# LTC3829_EVB.net
KiCad netlist of a schematic drawn in Altium Designer
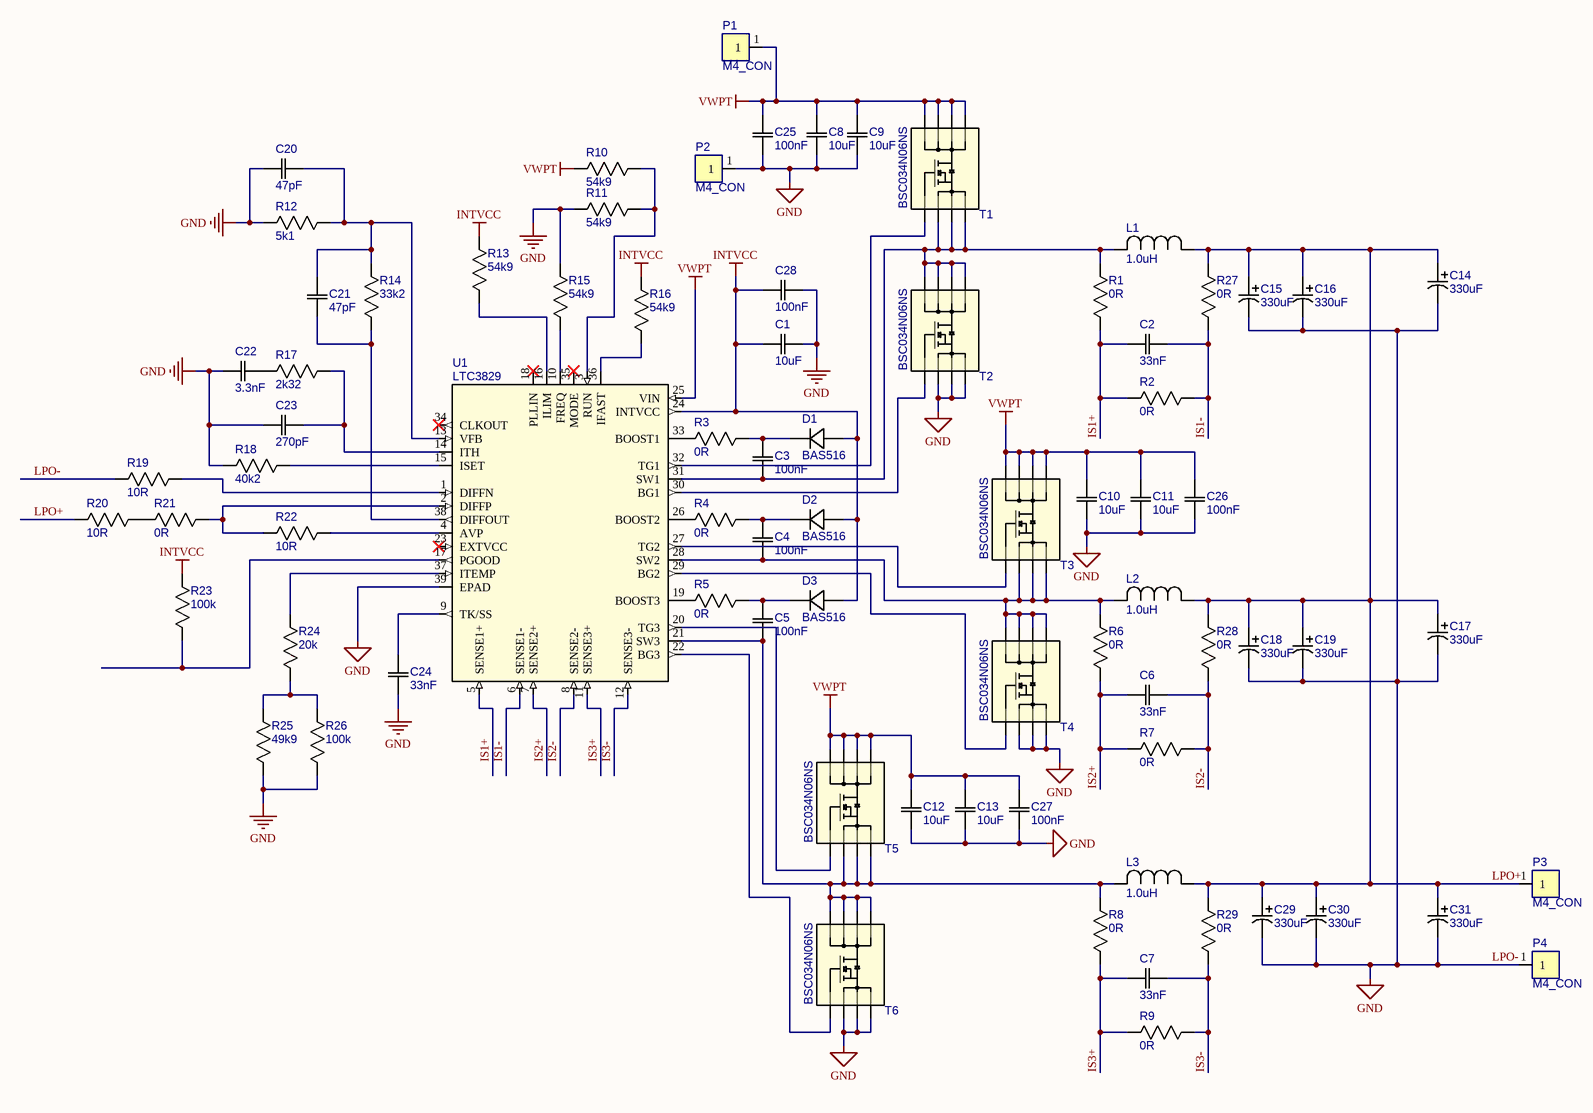
[diagram p0: LTC3829_EVB.SchDoc]

(export (version "E")
  (design (tool "Eeschema 10.0.6"))
  (components
    (comp (ref "C1")
      (value "10uF")
      (footprint "C0603")
      (description "OUDEIBUN\r\n25V 10% 106K X5R")
      (fields (field (name "MFR.") "OUDEIBUN"))
      (libsource (lib "C0603") (part "OUDEIBUN_10uF_25V"))
    )
    (comp (ref "C2")
      (value "33nF")
      (footprint "0402")
      (description "0402 33nF 333K 16V X7R")
      (fields (field (name "MFR.") "OBEIDUN"))
      (libsource (lib "C0402") (part "OBEIDUN_33nF"))
    )
    (comp (ref "C3")
      (value "100nF")
      (footprint "0402")
      (description "0402 100NF 104K  50V X7R")
      (fields (field (name "MFR.") "OBEIDUN"))
      (libsource (lib "C0402") (part "OBEIDUN_100nF"))
    )
    (comp (ref "C4")
      (value "100nF")
      (footprint "0402")
      (description "0402 100NF 104K  50V X7R")
      (fields (field (name "MFR.") "OBEIDUN"))
      (libsource (lib "C0402") (part "OBEIDUN_100nF"))
    )
    (comp (ref "C5")
      (value "100nF")
      (footprint "0402")
      (description "0402 100NF 104K  50V X7R")
      (fields (field (name "MFR.") "OBEIDUN"))
      (libsource (lib "C0402") (part "OBEIDUN_100nF"))
    )
    (comp (ref "C6")
      (value "33nF")
      (footprint "0402")
      (description "0402 33nF 333K 16V X7R")
      (fields (field (name "MFR.") "OBEIDUN"))
      (libsource (lib "C0402") (part "OBEIDUN_33nF"))
    )
    (comp (ref "C7")
      (value "33nF")
      (footprint "0402")
      (description "0402 33nF 333K 16V X7R")
      (fields (field (name "MFR.") "OBEIDUN"))
      (libsource (lib "C0402") (part "OBEIDUN_33nF"))
    )
    (comp (ref "C8")
      (value "10uF")
      (footprint "1210")
      (description "1210 10UF 106K 100V X7R")
      (fields (field (name "MFR.") "OUBEIDUN"))
      (libsource (lib "C1210") (part "OUBEIDUN_106_X7R"))
    )
    (comp (ref "C9")
      (value "10uF")
      (footprint "1210")
      (description "1210 10UF 106K 100V X7R")
      (fields (field (name "MFR.") "OUBEIDUN"))
      (libsource (lib "C1210") (part "OUBEIDUN_106_X7R"))
    )
    (comp (ref "C10")
      (value "10uF")
      (footprint "1210")
      (description "1210 10UF 106K 100V X7R")
      (fields (field (name "MFR.") "OUBEIDUN"))
      (libsource (lib "C1210") (part "OUBEIDUN_106_X7R"))
    )
    (comp (ref "C11")
      (value "10uF")
      (footprint "1210")
      (description "1210 10UF 106K 100V X7R")
      (fields (field (name "MFR.") "OUBEIDUN"))
      (libsource (lib "C1210") (part "OUBEIDUN_106_X7R"))
    )
    (comp (ref "C12")
      (value "10uF")
      (footprint "1210")
      (description "1210 10UF 106K 100V X7R")
      (fields (field (name "MFR.") "OUBEIDUN"))
      (libsource (lib "C1210") (part "OUBEIDUN_106_X7R"))
    )
    (comp (ref "C13")
      (value "10uF")
      (footprint "1210")
      (description "1210 10UF 106K 100V X7R")
      (fields (field (name "MFR.") "OUBEIDUN"))
      (libsource (lib "C1210") (part "OUBEIDUN_106_X7R"))
    )
    (comp (ref "C14")
      (value "330uF")
      (footprint "TAJD_AVX")
      (description "T520D337M006ATE010\r\n6.3V 330uF 2917 20% ESR=10mOhms")
      (fields (field (name "MFR.") "Auwah"))
      (libsource (lib "T520D337M006ATE010") (part "Auwah_330UF_7343"))
    )
    (comp (ref "C15")
      (value "330uF")
      (footprint "TAJD_AVX")
      (description "T520D337M006ATE010\r\n6.3V 330uF 2917 20% ESR=10mOhms")
      (fields (field (name "MFR.") "Auwah"))
      (libsource (lib "T520D337M006ATE010") (part "Auwah_330UF_7343"))
    )
    (comp (ref "C16")
      (value "330uF")
      (footprint "TAJD_AVX")
      (description "T520D337M006ATE010\r\n6.3V 330uF 2917 20% ESR=10mOhms")
      (fields (field (name "MFR.") "Auwah"))
      (libsource (lib "T520D337M006ATE010") (part "Auwah_330UF_7343"))
    )
    (comp (ref "C17")
      (value "330uF")
      (footprint "TAJD_AVX")
      (description "T520D337M006ATE010\r\n6.3V 330uF 2917 20% ESR=10mOhms")
      (fields (field (name "MFR.") "Auwah"))
      (libsource (lib "T520D337M006ATE010") (part "Auwah_330UF_7343"))
    )
    (comp (ref "C18")
      (value "330uF")
      (footprint "TAJD_AVX")
      (description "T520D337M006ATE010\r\n6.3V 330uF 2917 20% ESR=10mOhms")
      (fields (field (name "MFR.") "Auwah"))
      (libsource (lib "T520D337M006ATE010") (part "Auwah_330UF_7343"))
    )
    (comp (ref "C19")
      (value "330uF")
      (footprint "TAJD_AVX")
      (description "T520D337M006ATE010\r\n6.3V 330uF 2917 20% ESR=10mOhms")
      (fields (field (name "MFR.") "Auwah"))
      (libsource (lib "T520D337M006ATE010") (part "Auwah_330UF_7343"))
    )
    (comp (ref "C20")
      (value "47pF")
      (footprint "0402")
      (description "47pF 50V C0G CL05C470JB5NN4C")
      (fields (field (name "MFR.") "Samsung"))
      (libsource (lib "C0402") (part "taobao_47pF"))
    )
    (comp (ref "C21")
      (value "47pF")
      (footprint "0402")
      (description "47pF 50V C0G CL05C470JB5NN4C")
      (fields (field (name "MFR.") "Samsung"))
      (libsource (lib "C0402") (part "taobao_47pF"))
    )
    (comp (ref "C22")
      (value "3.3nF")
      (footprint "0402")
      (description "RAINPOLE 0402 3.3nF 5% 50V NPO")
      (fields (field (name "MFR.") "RAINPOLE"))
      (libsource (lib "C0402") (part "RAINPOLE_3n3F"))
    )
    (comp (ref "C23")
      (value "270pF")
      (footprint "0402")
      (description "0402 270PF 50V 271J COG NPO")
      (fields (field (name "MFR.") "OBEIDUN"))
      (libsource (lib "C0402") (part "OBEIDUN_270pF"))
    )
    (comp (ref "C24")
      (value "33nF")
      (footprint "0402")
      (description "0402 33nF 333K 16V X7R")
      (fields (field (name "MFR.") "OBEIDUN"))
      (libsource (lib "C0402") (part "OBEIDUN_33nF"))
    )
    (comp (ref "C25")
      (value "100nF")
      (footprint "C0603")
      (description "0603 100NF 50V 10% 104K X7R")
      (fields (field (name "MFR.") "OUDEIBUN"))
      (libsource (lib "C0603") (part "OUDEIBUN_100nF"))
    )
    (comp (ref "C26")
      (value "100nF")
      (footprint "C0603")
      (description "0603 100NF 50V 10% 104K X7R")
      (fields (field (name "MFR.") "OUDEIBUN"))
      (libsource (lib "C0603") (part "OUDEIBUN_100nF"))
    )
    (comp (ref "C27")
      (value "100nF")
      (footprint "C0603")
      (description "0603 100NF 50V 10% 104K X7R")
      (fields (field (name "MFR.") "OUDEIBUN"))
      (libsource (lib "C0603") (part "OUDEIBUN_100nF"))
    )
    (comp (ref "C28")
      (value "100nF")
      (footprint "0402")
      (description "0402 100NF 104K  50V X7R")
      (fields (field (name "MFR.") "OBEIDUN"))
      (libsource (lib "C0402") (part "OBEIDUN_100nF"))
    )
    (comp (ref "C29")
      (value "330uF")
      (footprint "TAJD_AVX")
      (description "T520D337M006ATE010\r\n6.3V 330uF 2917 20% ESR=10mOhms")
      (fields (field (name "MFR.") "Auwah"))
      (libsource (lib "T520D337M006ATE010") (part "Auwah_330UF_7343"))
    )
    (comp (ref "C30")
      (value "330uF")
      (footprint "TAJD_AVX")
      (description "T520D337M006ATE010\r\n6.3V 330uF 2917 20% ESR=10mOhms")
      (fields (field (name "MFR.") "Auwah"))
      (libsource (lib "T520D337M006ATE010") (part "Auwah_330UF_7343"))
    )
    (comp (ref "C31")
      (value "330uF")
      (footprint "TAJD_AVX")
      (description "T520D337M006ATE010\r\n6.3V 330uF 2917 20% ESR=10mOhms")
      (fields (field (name "MFR.") "Auwah"))
      (libsource (lib "T520D337M006ATE010") (part "Auwah_330UF_7343"))
    )
    (comp (ref "D1")
      (value "BAS516")
      (footprint "SOD-523")
      (description "SOD-523 100V/250mA")
      (fields (field (name "MFR.") "OBEIDUN"))
      (libsource (lib "BAS516") (part "OBEIDUN_BAS516"))
    )
    (comp (ref "D2")
      (value "BAS516")
      (footprint "SOD-523")
      (description "SOD-523 100V/250mA")
      (fields (field (name "MFR.") "OBEIDUN"))
      (libsource (lib "BAS516") (part "OBEIDUN_BAS516"))
    )
    (comp (ref "D3")
      (value "BAS516")
      (footprint "SOD-523")
      (description "SOD-523 100V/250mA")
      (fields (field (name "MFR.") "OBEIDUN"))
      (libsource (lib "BAS516") (part "OBEIDUN_BAS516"))
    )
    (comp (ref "L1")
      (value "1.0uH")
      (footprint "L126X")
      (description "HC1260 1R0M")
      (fields (field (name "MFR.") "HuiCi"))
      (libsource (lib "L12x0") (part "L1260_102"))
    )
    (comp (ref "L2")
      (value "1.0uH")
      (footprint "L126X")
      (description "HC1260 1R0M")
      (fields (field (name "MFR.") "HuiCi"))
      (libsource (lib "L12x0") (part "L1260_102"))
    )
    (comp (ref "L3")
      (value "1.0uH")
      (footprint "L126X")
      (description "HC1260 1R0M")
      (fields (field (name "MFR.") "HuiCi"))
      (libsource (lib "L12x0") (part "L1260_102"))
    )
    (comp (ref "P1")
      (value "M4_CON")
      (footprint "PCBComponent_1")
      (fields (field (name "MFR.") "LFX"))
      (libsource (lib "") (part "M4_CON_1"))
    )
    (comp (ref "P2")
      (value "M4_CON")
      (footprint "PCBComponent_1")
      (fields (field (name "MFR.") "LFX"))
      (libsource (lib "") (part "M4_CON_1"))
    )
    (comp (ref "P3")
      (value "M4_CON")
      (footprint "PCBComponent_1")
      (fields (field (name "MFR.") "LFX"))
      (libsource (lib "M4_CON") (part "M4_CON"))
    )
    (comp (ref "P4")
      (value "M4_CON")
      (footprint "PCBComponent_1")
      (fields (field (name "MFR.") "LFX"))
      (libsource (lib "M4_CON") (part "M4_CON"))
    )
    (comp (ref "R1")
      (value "0R")
      (footprint "0402")
      (description "OUDEIBUN\r\n0R 1% 1/16W")
      (fields (field (name "MFR.") "OUDEIBUN"))
      (libsource (lib "R0402") (part "OUDEIBUN_0R"))
    )
    (comp (ref "R2")
      (value "0R")
      (footprint "0402")
      (description "OUDEIBUN\r\n0R 1% 1/16W")
      (fields (field (name "MFR.") "OUDEIBUN"))
      (libsource (lib "R0402") (part "OUDEIBUN_0R"))
    )
    (comp (ref "R3")
      (value "0R")
      (footprint "0603")
      (description "0R 1/10W +/-1%")
      (fields (field (name "MFR.") "UNIOHM"))
      (libsource (lib "R0603") (part "0R"))
    )
    (comp (ref "R4")
      (value "0R")
      (footprint "0603")
      (description "0R 1/10W +/-1%")
      (fields (field (name "MFR.") "UNIOHM"))
      (libsource (lib "R0603") (part "0R"))
    )
    (comp (ref "R5")
      (value "0R")
      (footprint "0603")
      (description "0R 1/10W +/-1%")
      (fields (field (name "MFR.") "UNIOHM"))
      (libsource (lib "R0603") (part "0R"))
    )
    (comp (ref "R6")
      (value "0R")
      (footprint "0402")
      (description "OUDEIBUN\r\n0R 1% 1/16W")
      (fields (field (name "MFR.") "OUDEIBUN"))
      (libsource (lib "R0402") (part "OUDEIBUN_0R"))
    )
    (comp (ref "R7")
      (value "0R")
      (footprint "0402")
      (description "OUDEIBUN\r\n0R 1% 1/16W")
      (fields (field (name "MFR.") "OUDEIBUN"))
      (libsource (lib "R0402") (part "OUDEIBUN_0R"))
    )
    (comp (ref "R8")
      (value "0R")
      (footprint "0402")
      (description "OUDEIBUN\r\n0R 1% 1/16W")
      (fields (field (name "MFR.") "OUDEIBUN"))
      (libsource (lib "R0402") (part "OUDEIBUN_0R"))
    )
    (comp (ref "R9")
      (value "0R")
      (footprint "0402")
      (description "OUDEIBUN\r\n0R 1% 1/16W")
      (fields (field (name "MFR.") "OUDEIBUN"))
      (libsource (lib "R0402") (part "OUDEIBUN_0R"))
    )
    (comp (ref "R10")
      (value "54k9")
      (footprint "0402")
      (description "OUDEIBUN\r\n54k9 1% 1/16W")
      (fields (field (name "MFR.") "OUDEIBUN"))
      (libsource (lib "R0402") (part "OUDEIBUN_54k9"))
    )
    (comp (ref "R11")
      (value "54k9")
      (footprint "0402")
      (description "OUDEIBUN\r\n54k9 1% 1/16W")
      (fields (field (name "MFR.") "OUDEIBUN"))
      (libsource (lib "R0402") (part "OUDEIBUN_54k9"))
    )
    (comp (ref "R12")
      (value "5k1")
      (footprint "0402")
      (description "UNIOHM\r\n5k1 1% 1/16W")
      (fields (field (name "MFR.") "UNIOHM"))
      (libsource (lib "R0402") (part "UNIOHM_5k1"))
    )
    (comp (ref "R13")
      (value "54k9")
      (footprint "0402")
      (description "OUDEIBUN\r\n54k9 1% 1/16W")
      (fields (field (name "MFR.") "OUDEIBUN"))
      (libsource (lib "R0402") (part "OUDEIBUN_54k9"))
    )
    (comp (ref "R14")
      (value "33k2")
      (footprint "0402")
      (description "OUDEIBUN\r\n33k2 1% 1/16W")
      (fields (field (name "MFR.") "OUDEIBUN"))
      (libsource (lib "R0402") (part "OUDEIBUN_33k2"))
    )
    (comp (ref "R15")
      (value "54k9")
      (footprint "0402")
      (description "OUDEIBUN\r\n54k9 1% 1/16W")
      (fields (field (name "MFR.") "OUDEIBUN"))
      (libsource (lib "R0402") (part "OUDEIBUN_54k9"))
    )
    (comp (ref "R16")
      (value "54k9")
      (footprint "0402")
      (description "OUDEIBUN\r\n54k9 1% 1/16W")
      (fields (field (name "MFR.") "OUDEIBUN"))
      (libsource (lib "R0402") (part "OUDEIBUN_54k9"))
    )
    (comp (ref "R17")
      (value "2k32")
      (footprint "0402")
      (description "OUDEIBUN\r\n1% 2k32")
      (fields (field (name "MFR.") "OUDEIBUN"))
      (libsource (lib "R0402") (part "OUDEIBUN_2k32"))
    )
    (comp (ref "R18")
      (value "40k2")
      (footprint "0402")
      (description "UNIOHM\r\n40k2 1% 1/16W")
      (fields (field (name "MFR.") "UNIOHM"))
      (libsource (lib "R0402") (part "UNIOHM_40k2"))
    )
    (comp (ref "R19")
      (value "10R")
      (footprint "0402")
      (description "OUDEIBUN\r\n10R 1% 1/16W")
      (fields (field (name "MFR.") "OUDEIBUN"))
      (libsource (lib "R0402") (part "OUDEIBUN_10R"))
    )
    (comp (ref "R20")
      (value "10R")
      (footprint "0402")
      (description "OUDEIBUN\r\n10R 1% 1/16W")
      (fields (field (name "MFR.") "OUDEIBUN"))
      (libsource (lib "R0402") (part "OUDEIBUN_10R"))
    )
    (comp (ref "R21")
      (value "0R")
      (footprint "0402")
      (description "OUDEIBUN\r\n0R 1% 1/16W")
      (fields (field (name "MFR.") "OUDEIBUN"))
      (libsource (lib "R0402") (part "OUDEIBUN_0R"))
    )
    (comp (ref "R22")
      (value "10R")
      (footprint "0603")
      (description "10R 1/10W +/-0.5%")
      (fields (field (name "MFR.") "Viking"))
      (libsource (lib "R0603") (part "ARG03DTC0100"))
    )
    (comp (ref "R23")
      (value "100k")
      (footprint "0402")
      (description "OUDEIBUN\r\n1% 100k")
      (fields (field (name "MFR.") "UNIOHM"))
      (libsource (lib "R0402") (part "OUDEIBUN_100k"))
    )
    (comp (ref "R24")
      (value "20k")
      (footprint "0402")
      (description "OUDEIBUN\r\n20k 1% 1/16W")
      (fields (field (name "MFR.") "OUDEIBUN"))
      (libsource (lib "R0402") (part "OUDEIBUN_20k"))
    )
    (comp (ref "R25")
      (value "49k9")
      (footprint "0402")
      (description "OUDEIBUN\r\n1% 49k9")
      (fields (field (name "MFR.") "OUDEIBUN"))
      (libsource (lib "R0402") (part "OUDEIBUN_49k9"))
    )
    (comp (ref "R26")
      (value "100k")
      (footprint "0402")
      (description "OUDEIBUN\r\n1% 100k")
      (fields (field (name "MFR.") "UNIOHM"))
      (libsource (lib "R0402") (part "OUDEIBUN_100k"))
    )
    (comp (ref "R27")
      (value "0R")
      (footprint "0402")
      (description "OUDEIBUN\r\n0R 1% 1/16W")
      (fields (field (name "MFR.") "OUDEIBUN"))
      (libsource (lib "R0402") (part "OUDEIBUN_0R"))
    )
    (comp (ref "R28")
      (value "0R")
      (footprint "0402")
      (description "OUDEIBUN\r\n0R 1% 1/16W")
      (fields (field (name "MFR.") "OUDEIBUN"))
      (libsource (lib "R0402") (part "OUDEIBUN_0R"))
    )
    (comp (ref "R29")
      (value "0R")
      (footprint "0402")
      (description "OUDEIBUN\r\n0R 1% 1/16W")
      (fields (field (name "MFR.") "OUDEIBUN"))
      (libsource (lib "R0402") (part "OUDEIBUN_0R"))
    )
    (comp (ref "T1")
      (value "BSC034N06NS")
      (footprint "PQFNWB5x6")
      (description "MPower Transistor, 60V")
      (fields (field (name "MFR.") "Infineon Technologies"))
      (libsource (lib "MOS_PQFNWB5x6") (part "BSC034N06NS"))
    )
    (comp (ref "T2")
      (value "BSC034N06NS")
      (footprint "PQFNWB5x6")
      (description "MPower Transistor, 60V")
      (fields (field (name "MFR.") "Infineon Technologies"))
      (libsource (lib "MOS_PQFNWB5x6") (part "BSC034N06NS"))
    )
    (comp (ref "T3")
      (value "BSC034N06NS")
      (footprint "PQFNWB5x6")
      (description "MPower Transistor, 60V")
      (fields (field (name "MFR.") "Infineon Technologies"))
      (libsource (lib "MOS_PQFNWB5x6") (part "BSC034N06NS"))
    )
    (comp (ref "T4")
      (value "BSC034N06NS")
      (footprint "PQFNWB5x6")
      (description "MPower Transistor, 60V")
      (fields (field (name "MFR.") "Infineon Technologies"))
      (libsource (lib "MOS_PQFNWB5x6") (part "BSC034N06NS"))
    )
    (comp (ref "T5")
      (value "BSC034N06NS")
      (footprint "PQFNWB5x6")
      (description "MPower Transistor, 60V")
      (fields (field (name "MFR.") "Infineon Technologies"))
      (libsource (lib "MOS_PQFNWB5x6") (part "BSC034N06NS"))
    )
    (comp (ref "T6")
      (value "BSC034N06NS")
      (footprint "PQFNWB5x6")
      (description "MPower Transistor, 60V")
      (fields (field (name "MFR.") "Infineon Technologies"))
      (libsource (lib "MOS_PQFNWB5x6") (part "BSC034N06NS"))
    )
    (comp (ref "U1")
      (value "LTC3829")
      (footprint "QFN-38")
      (description "3-Phase, Single Output Synchronous\r\nStep-Down DC/DC Controller with Diffamp")
      (fields (field (name "MFR.") "Analog Devices Inc"))
      (libsource (lib "LTC3829") (part "LTC3829EUHFPBF"))
    )
  )
  (nets
    (net (code "1") (name "/IS1+") (class "Default")
      (node (ref "C2") (pin "1") (pinfunction "1_1") (pintype "passive"))
      (node (ref "R1") (pin "1") (pinfunction "1_1") (pintype "passive"))
      (node (ref "R2") (pin "2") (pinfunction "2_2") (pintype "passive"))
      (node (ref "U1") (pin "5") (pinfunction "SENSE1+_5") (pintype "input"))
    )
    (net (code "2") (name "/IS1-") (class "Default")
      (node (ref "C2") (pin "2") (pinfunction "2_2") (pintype "passive"))
      (node (ref "R2") (pin "1") (pinfunction "1_1") (pintype "passive"))
      (node (ref "R27") (pin "1") (pinfunction "1_1") (pintype "passive"))
      (node (ref "U1") (pin "6") (pinfunction "SENSE1-_6") (pintype "input"))
    )
    (net (code "3") (name "/IS2+") (class "Default")
      (node (ref "C6") (pin "1") (pinfunction "1_1") (pintype "passive"))
      (node (ref "R6") (pin "1") (pinfunction "1_1") (pintype "passive"))
      (node (ref "R7") (pin "2") (pinfunction "2_2") (pintype "passive"))
      (node (ref "U1") (pin "7") (pinfunction "SENSE2+_7") (pintype "input"))
    )
    (net (code "4") (name "/IS2-") (class "Default")
      (node (ref "C6") (pin "2") (pinfunction "2_2") (pintype "passive"))
      (node (ref "R28") (pin "1") (pinfunction "1_1") (pintype "passive"))
      (node (ref "R7") (pin "1") (pinfunction "1_1") (pintype "passive"))
      (node (ref "U1") (pin "8") (pinfunction "SENSE2-_8") (pintype "input"))
    )
    (net (code "5") (name "/IS3+") (class "Default")
      (node (ref "C7") (pin "1") (pinfunction "1_1") (pintype "passive"))
      (node (ref "R8") (pin "1") (pinfunction "1_1") (pintype "passive"))
      (node (ref "R9") (pin "2") (pinfunction "2_2") (pintype "passive"))
      (node (ref "U1") (pin "11") (pinfunction "SENSE3+_11") (pintype "input"))
    )
    (net (code "6") (name "/IS3-") (class "Default")
      (node (ref "C7") (pin "2") (pinfunction "2_2") (pintype "passive"))
      (node (ref "R29") (pin "1") (pinfunction "1_1") (pintype "passive"))
      (node (ref "R9") (pin "1") (pinfunction "1_1") (pintype "passive"))
      (node (ref "U1") (pin "12") (pinfunction "SENSE3-_12") (pintype "input"))
    )
    (net (code "7") (name "/LPO+") (class "Default")
      (node (ref "C14") (pin "1") (pinfunction "11_1") (pintype "passive"))
      (node (ref "C15") (pin "1") (pinfunction "11_1") (pintype "passive"))
      (node (ref "C16") (pin "1") (pinfunction "11_1") (pintype "passive"))
      (node (ref "C17") (pin "1") (pinfunction "11_1") (pintype "passive"))
      (node (ref "C18") (pin "1") (pinfunction "11_1") (pintype "passive"))
      (node (ref "C19") (pin "1") (pinfunction "11_1") (pintype "passive"))
      (node (ref "C29") (pin "1") (pinfunction "11_1") (pintype "passive"))
      (node (ref "C30") (pin "1") (pinfunction "11_1") (pintype "passive"))
      (node (ref "C31") (pin "1") (pinfunction "11_1") (pintype "passive"))
      (node (ref "L1") (pin "1") (pinfunction "1_1") (pintype "passive"))
      (node (ref "L2") (pin "1") (pinfunction "1_1") (pintype "passive"))
      (node (ref "L3") (pin "1") (pinfunction "1_1") (pintype "passive"))
      (node (ref "P3") (pin "1") (pinfunction "1_1") (pintype "passive"))
      (node (ref "R20") (pin "1") (pinfunction "1_1") (pintype "passive"))
      (node (ref "R27") (pin "2") (pinfunction "2_2") (pintype "passive"))
      (node (ref "R28") (pin "2") (pinfunction "2_2") (pintype "passive"))
      (node (ref "R29") (pin "2") (pinfunction "2_2") (pintype "passive"))
    )
    (net (code "8") (name "GND") (class "Default")
      (node (ref "C1") (pin "2") (pinfunction "2_2") (pintype "passive"))
      (node (ref "C10") (pin "1") (pinfunction "11_1") (pintype "passive"))
      (node (ref "C11") (pin "1") (pinfunction "11_1") (pintype "passive"))
      (node (ref "C12") (pin "1") (pinfunction "11_1") (pintype "passive"))
      (node (ref "C13") (pin "1") (pinfunction "11_1") (pintype "passive"))
      (node (ref "C14") (pin "2") (pinfunction "12_2") (pintype "passive"))
      (node (ref "C15") (pin "2") (pinfunction "12_2") (pintype "passive"))
      (node (ref "C16") (pin "2") (pinfunction "12_2") (pintype "passive"))
      (node (ref "C17") (pin "2") (pinfunction "12_2") (pintype "passive"))
      (node (ref "C18") (pin "2") (pinfunction "12_2") (pintype "passive"))
      (node (ref "C19") (pin "2") (pinfunction "12_2") (pintype "passive"))
      (node (ref "C20") (pin "1") (pinfunction "1_1") (pintype "passive"))
      (node (ref "C22") (pin "1") (pinfunction "1_1") (pintype "passive"))
      (node (ref "C23") (pin "1") (pinfunction "1_1") (pintype "passive"))
      (node (ref "C24") (pin "1") (pinfunction "1_1") (pintype "passive"))
      (node (ref "C25") (pin "1") (pinfunction "1_1") (pintype "passive"))
      (node (ref "C26") (pin "1") (pinfunction "1_1") (pintype "passive"))
      (node (ref "C27") (pin "1") (pinfunction "1_1") (pintype "passive"))
      (node (ref "C28") (pin "1") (pinfunction "1_1") (pintype "passive"))
      (node (ref "C29") (pin "2") (pinfunction "12_2") (pintype "passive"))
      (node (ref "C30") (pin "2") (pinfunction "12_2") (pintype "passive"))
      (node (ref "C31") (pin "2") (pinfunction "12_2") (pintype "passive"))
      (node (ref "C8") (pin "1") (pinfunction "11_1") (pintype "passive"))
      (node (ref "C9") (pin "1") (pinfunction "11_1") (pintype "passive"))
      (node (ref "P2") (pin "1") (pinfunction "1_1") (pintype "passive"))
      (node (ref "P4") (pin "1") (pinfunction "1_1") (pintype "passive"))
      (node (ref "R11") (pin "2") (pinfunction "2_2") (pintype "passive"))
      (node (ref "R12") (pin "1") (pinfunction "1_1") (pintype "passive"))
      (node (ref "R15") (pin "2") (pinfunction "2_2") (pintype "passive"))
      (node (ref "R18") (pin "1") (pinfunction "1_1") (pintype "passive"))
      (node (ref "R19") (pin "1") (pinfunction "1_1") (pintype "passive"))
      (node (ref "R25") (pin "1") (pinfunction "1_1") (pintype "passive"))
      (node (ref "R26") (pin "1") (pinfunction "1_1") (pintype "passive"))
      (node (ref "T2") (pin "1") (pinfunction "1_1") (pintype "passive"))
      (node (ref "T2") (pin "2") (pinfunction "2_2") (pintype "passive"))
      (node (ref "T2") (pin "3") (pinfunction "3_3") (pintype "passive"))
      (node (ref "T4") (pin "1") (pinfunction "1_1") (pintype "passive"))
      (node (ref "T4") (pin "2") (pinfunction "2_2") (pintype "passive"))
      (node (ref "T4") (pin "3") (pinfunction "3_3") (pintype "passive"))
      (node (ref "T6") (pin "1") (pinfunction "1_1") (pintype "passive"))
      (node (ref "T6") (pin "2") (pinfunction "2_2") (pintype "passive"))
      (node (ref "T6") (pin "3") (pinfunction "3_3") (pintype "passive"))
      (node (ref "U1") (pin "39") (pinfunction "EPAD_39") (pintype "passive"))
    )
    (net (code "9") (name "INTVCC") (class "Default")
      (node (ref "C1") (pin "1") (pinfunction "1_1") (pintype "passive"))
      (node (ref "C28") (pin "2") (pinfunction "2_2") (pintype "passive"))
      (node (ref "D1") (pin "2") (pinfunction "2_2") (pintype "passive"))
      (node (ref "D2") (pin "2") (pinfunction "2_2") (pintype "passive"))
      (node (ref "D3") (pin "2") (pinfunction "2_2") (pintype "passive"))
      (node (ref "R13") (pin "2") (pinfunction "2_2") (pintype "passive"))
      (node (ref "R16") (pin "2") (pinfunction "2_2") (pintype "passive"))
      (node (ref "R23") (pin "2") (pinfunction "2_2") (pintype "passive"))
      (node (ref "U1") (pin "24") (pinfunction "INTVCC_24") (pintype "output"))
    )
    (net (code "10") (name "Net-(C3-Pad2)") (class "Default")
      (node (ref "C3") (pin "2") (pinfunction "2_2") (pintype "passive"))
      (node (ref "D1") (pin "1") (pinfunction "1_1") (pintype "passive"))
      (node (ref "R3") (pin "2") (pinfunction "2_2") (pintype "passive"))
    )
    (net (code "11") (name "Net-(C4-Pad2)") (class "Default")
      (node (ref "C4") (pin "2") (pinfunction "2_2") (pintype "passive"))
      (node (ref "D2") (pin "1") (pinfunction "1_1") (pintype "passive"))
      (node (ref "R4") (pin "2") (pinfunction "2_2") (pintype "passive"))
    )
    (net (code "12") (name "Net-(C5-Pad2)") (class "Default")
      (node (ref "C5") (pin "2") (pinfunction "2_2") (pintype "passive"))
      (node (ref "D3") (pin "1") (pinfunction "1_1") (pintype "passive"))
      (node (ref "R5") (pin "2") (pinfunction "2_2") (pintype "passive"))
    )
    (net (code "13") (name "Net-(C22-Pad2)") (class "Default")
      (node (ref "C22") (pin "2") (pinfunction "2_2") (pintype "passive"))
      (node (ref "R17") (pin "1") (pinfunction "1_1") (pintype "passive"))
    )
    (net (code "14") (name "Net-(R20-Pad2)") (class "Default")
      (node (ref "R20") (pin "2") (pinfunction "2_2") (pintype "passive"))
      (node (ref "R21") (pin "1") (pinfunction "1_1") (pintype "passive"))
    )
    (net (code "15") (name "Net-(R24-Pad1)") (class "Default")
      (node (ref "R24") (pin "1") (pinfunction "1_1") (pintype "passive"))
      (node (ref "R25") (pin "2") (pinfunction "2_2") (pintype "passive"))
      (node (ref "R26") (pin "2") (pinfunction "2_2") (pintype "passive"))
    )
    (net (code "16") (name "Net-(U1-AVP)") (class "Default")
      (node (ref "R22") (pin "2") (pinfunction "2_2") (pintype "passive"))
      (node (ref "U1") (pin "4") (pinfunction "AVP_4") (pintype "passive"))
    )
    (net (code "17") (name "Net-(U1-BG1)") (class "Default")
      (node (ref "T2") (pin "4") (pinfunction "4_4") (pintype "passive"))
      (node (ref "U1") (pin "30") (pinfunction "BG1_30") (pintype "output"))
    )
    (net (code "18") (name "Net-(U1-BG2)") (class "Default")
      (node (ref "T4") (pin "4") (pinfunction "4_4") (pintype "passive"))
      (node (ref "U1") (pin "29") (pinfunction "BG2_29") (pintype "output"))
    )
    (net (code "19") (name "Net-(U1-BG3)") (class "Default")
      (node (ref "T6") (pin "4") (pinfunction "4_4") (pintype "passive"))
      (node (ref "U1") (pin "22") (pinfunction "BG3_22") (pintype "output"))
    )
    (net (code "20") (name "Net-(U1-BOOST1)") (class "Default")
      (node (ref "R3") (pin "1") (pinfunction "1_1") (pintype "passive"))
      (node (ref "U1") (pin "33") (pinfunction "BOOST1_33") (pintype "passive"))
    )
    (net (code "21") (name "Net-(U1-BOOST2)") (class "Default")
      (node (ref "R4") (pin "1") (pinfunction "1_1") (pintype "passive"))
      (node (ref "U1") (pin "26") (pinfunction "BOOST2_26") (pintype "passive"))
    )
    (net (code "22") (name "Net-(U1-BOOST3)") (class "Default")
      (node (ref "R5") (pin "1") (pinfunction "1_1") (pintype "passive"))
      (node (ref "U1") (pin "19") (pinfunction "BOOST3_19") (pintype "passive"))
    )
    (net (code "23") (name "Net-(U1-DIFFN)") (class "Default")
      (node (ref "R19") (pin "2") (pinfunction "2_2") (pintype "passive"))
      (node (ref "U1") (pin "1") (pinfunction "DIFFN_1") (pintype "input"))
    )
    (net (code "24") (name "Net-(U1-DIFFOUT)") (class "Default")
      (node (ref "C21") (pin "1") (pinfunction "1_1") (pintype "passive"))
      (node (ref "R14") (pin "1") (pinfunction "1_1") (pintype "passive"))
      (node (ref "U1") (pin "38") (pinfunction "DIFFOUT_38") (pintype "output"))
    )
    (net (code "25") (name "Net-(U1-DIFFP)") (class "Default")
      (node (ref "R21") (pin "2") (pinfunction "2_2") (pintype "passive"))
      (node (ref "R22") (pin "1") (pinfunction "1_1") (pintype "passive"))
      (node (ref "U1") (pin "2") (pinfunction "DIFFP_2") (pintype "input"))
    )
    (net (code "26") (name "Net-(U1-FREQ)") (class "Default")
      (node (ref "R15") (pin "1") (pinfunction "1_1") (pintype "passive"))
      (node (ref "U1") (pin "10") (pinfunction "FREQ_10") (pintype "passive"))
    )
    (net (code "27") (name "Net-(U1-IFAST)") (class "Default")
      (node (ref "R16") (pin "1") (pinfunction "1_1") (pintype "passive"))
      (node (ref "U1") (pin "36") (pinfunction "IFAST_36") (pintype "passive"))
    )
    (net (code "28") (name "Net-(U1-ILIM)") (class "Default")
      (node (ref "R13") (pin "1") (pinfunction "1_1") (pintype "passive"))
      (node (ref "U1") (pin "16") (pinfunction "ILIM_16") (pintype "passive"))
    )
    (net (code "29") (name "Net-(U1-ISET)") (class "Default")
      (node (ref "R18") (pin "2") (pinfunction "2_2") (pintype "passive"))
      (node (ref "U1") (pin "15") (pinfunction "ISET_15") (pintype "passive"))
    )
    (net (code "30") (name "Net-(U1-ITEMP)") (class "Default")
      (node (ref "R24") (pin "2") (pinfunction "2_2") (pintype "passive"))
      (node (ref "U1") (pin "37") (pinfunction "ITEMP_37") (pintype "input"))
    )
    (net (code "31") (name "Net-(U1-ITH)") (class "Default")
      (node (ref "C23") (pin "2") (pinfunction "2_2") (pintype "passive"))
      (node (ref "R17") (pin "2") (pinfunction "2_2") (pintype "passive"))
      (node (ref "U1") (pin "14") (pinfunction "ITH_14") (pintype "passive"))
    )
    (net (code "32") (name "Net-(U1-PGOOD)") (class "Default")
      (node (ref "R23") (pin "1") (pinfunction "1_1") (pintype "passive"))
      (node (ref "U1") (pin "17") (pinfunction "PGOOD_17") (pintype "output"))
    )
    (net (code "33") (name "Net-(U1-RUN)") (class "Default")
      (node (ref "R10") (pin "1") (pinfunction "1_1") (pintype "passive"))
      (node (ref "R11") (pin "1") (pinfunction "1_1") (pintype "passive"))
      (node (ref "U1") (pin "3") (pinfunction "RUN_3") (pintype "input"))
    )
    (net (code "34") (name "Net-(U1-SW1)") (class "Default")
      (node (ref "C3") (pin "1") (pinfunction "1_1") (pintype "passive"))
      (node (ref "L1") (pin "2") (pinfunction "2_2") (pintype "passive"))
      (node (ref "R1") (pin "2") (pinfunction "2_2") (pintype "passive"))
      (node (ref "T1") (pin "1") (pinfunction "1_1") (pintype "passive"))
      (node (ref "T1") (pin "2") (pinfunction "2_2") (pintype "passive"))
      (node (ref "T1") (pin "3") (pinfunction "3_3") (pintype "passive"))
      (node (ref "T2") (pin "5") (pinfunction "5_5") (pintype "passive"))
      (node (ref "T2") (pin "6") (pinfunction "6_6") (pintype "passive"))
      (node (ref "T2") (pin "7") (pinfunction "7_7") (pintype "passive"))
      (node (ref "T2") (pin "8") (pinfunction "8_8") (pintype "passive"))
      (node (ref "U1") (pin "31") (pinfunction "SW1_31") (pintype "passive"))
    )
    (net (code "35") (name "Net-(U1-SW2)") (class "Default")
      (node (ref "C4") (pin "1") (pinfunction "1_1") (pintype "passive"))
      (node (ref "L2") (pin "2") (pinfunction "2_2") (pintype "passive"))
      (node (ref "R6") (pin "2") (pinfunction "2_2") (pintype "passive"))
      (node (ref "T3") (pin "1") (pinfunction "1_1") (pintype "passive"))
      (node (ref "T3") (pin "2") (pinfunction "2_2") (pintype "passive"))
      (node (ref "T3") (pin "3") (pinfunction "3_3") (pintype "passive"))
      (node (ref "T4") (pin "5") (pinfunction "5_5") (pintype "passive"))
      (node (ref "T4") (pin "6") (pinfunction "6_6") (pintype "passive"))
      (node (ref "T4") (pin "7") (pinfunction "7_7") (pintype "passive"))
      (node (ref "T4") (pin "8") (pinfunction "8_8") (pintype "passive"))
      (node (ref "U1") (pin "28") (pinfunction "SW2_28") (pintype "passive"))
    )
    (net (code "36") (name "Net-(U1-SW3)") (class "Default")
      (node (ref "C5") (pin "1") (pinfunction "1_1") (pintype "passive"))
      (node (ref "L3") (pin "2") (pinfunction "2_2") (pintype "passive"))
      (node (ref "R8") (pin "2") (pinfunction "2_2") (pintype "passive"))
      (node (ref "T5") (pin "1") (pinfunction "1_1") (pintype "passive"))
      (node (ref "T5") (pin "2") (pinfunction "2_2") (pintype "passive"))
      (node (ref "T5") (pin "3") (pinfunction "3_3") (pintype "passive"))
      (node (ref "T6") (pin "5") (pinfunction "5_5") (pintype "passive"))
      (node (ref "T6") (pin "6") (pinfunction "6_6") (pintype "passive"))
      (node (ref "T6") (pin "7") (pinfunction "7_7") (pintype "passive"))
      (node (ref "T6") (pin "8") (pinfunction "8_8") (pintype "passive"))
      (node (ref "U1") (pin "21") (pinfunction "SW3_21") (pintype "passive"))
    )
    (net (code "37") (name "Net-(U1-TG1)") (class "Default")
      (node (ref "T1") (pin "4") (pinfunction "4_4") (pintype "passive"))
      (node (ref "U1") (pin "32") (pinfunction "TG1_32") (pintype "output"))
    )
    (net (code "38") (name "Net-(U1-TG2)") (class "Default")
      (node (ref "T3") (pin "4") (pinfunction "4_4") (pintype "passive"))
      (node (ref "U1") (pin "27") (pinfunction "TG2_27") (pintype "output"))
    )
    (net (code "39") (name "Net-(U1-TG3)") (class "Default")
      (node (ref "T5") (pin "4") (pinfunction "4_4") (pintype "passive"))
      (node (ref "U1") (pin "20") (pinfunction "TG3_20") (pintype "output"))
    )
    (net (code "40") (name "Net-(U1-TK{slash}SS)") (class "Default")
      (node (ref "C24") (pin "2") (pinfunction "2_2") (pintype "passive"))
      (node (ref "U1") (pin "9") (pinfunction "TK/SS_9") (pintype "output"))
    )
    (net (code "41") (name "Net-(U1-VFB)") (class "Default")
      (node (ref "C20") (pin "2") (pinfunction "2_2") (pintype "passive"))
      (node (ref "C21") (pin "2") (pinfunction "2_2") (pintype "passive"))
      (node (ref "R12") (pin "2") (pinfunction "2_2") (pintype "passive"))
      (node (ref "R14") (pin "2") (pinfunction "2_2") (pintype "passive"))
      (node (ref "U1") (pin "13") (pinfunction "VFB_13") (pintype "input"))
    )
    (net (code "42") (name "VWPT") (class "Default")
      (node (ref "C10") (pin "2") (pinfunction "12_2") (pintype "passive"))
      (node (ref "C11") (pin "2") (pinfunction "12_2") (pintype "passive"))
      (node (ref "C12") (pin "2") (pinfunction "12_2") (pintype "passive"))
      (node (ref "C13") (pin "2") (pinfunction "12_2") (pintype "passive"))
      (node (ref "C25") (pin "2") (pinfunction "2_2") (pintype "passive"))
      (node (ref "C26") (pin "2") (pinfunction "2_2") (pintype "passive"))
      (node (ref "C27") (pin "2") (pinfunction "2_2") (pintype "passive"))
      (node (ref "C8") (pin "2") (pinfunction "12_2") (pintype "passive"))
      (node (ref "C9") (pin "2") (pinfunction "12_2") (pintype "passive"))
      (node (ref "P1") (pin "1") (pinfunction "1_1") (pintype "passive"))
      (node (ref "R10") (pin "2") (pinfunction "2_2") (pintype "passive"))
      (node (ref "T1") (pin "5") (pinfunction "5_5") (pintype "passive"))
      (node (ref "T1") (pin "6") (pinfunction "6_6") (pintype "passive"))
      (node (ref "T1") (pin "7") (pinfunction "7_7") (pintype "passive"))
      (node (ref "T1") (pin "8") (pinfunction "8_8") (pintype "passive"))
      (node (ref "T3") (pin "5") (pinfunction "5_5") (pintype "passive"))
      (node (ref "T3") (pin "6") (pinfunction "6_6") (pintype "passive"))
      (node (ref "T3") (pin "7") (pinfunction "7_7") (pintype "passive"))
      (node (ref "T3") (pin "8") (pinfunction "8_8") (pintype "passive"))
      (node (ref "T5") (pin "5") (pinfunction "5_5") (pintype "passive"))
      (node (ref "T5") (pin "6") (pinfunction "6_6") (pintype "passive"))
      (node (ref "T5") (pin "7") (pinfunction "7_7") (pintype "passive"))
      (node (ref "T5") (pin "8") (pinfunction "8_8") (pintype "passive"))
      (node (ref "U1") (pin "25") (pinfunction "VIN_25") (pintype "input"))
    )
    (net (code "43") (name "unconnected-(U1-CLKOUT-Pad34)") (class "Default")
      (node (ref "U1") (pin "34") (pinfunction "CLKOUT_34") (pintype "output+no_connect"))
    )
    (net (code "44") (name "unconnected-(U1-EXTVCC-Pad23)") (class "Default")
      (node (ref "U1") (pin "23") (pinfunction "EXTVCC_23") (pintype "input+no_connect"))
    )
    (net (code "45") (name "unconnected-(U1-MODE-Pad35)") (class "Default")
      (node (ref "U1") (pin "35") (pinfunction "MODE_35") (pintype "passive+no_connect"))
    )
    (net (code "46") (name "unconnected-(U1-PLLIN-Pad18)") (class "Default")
      (node (ref "U1") (pin "18") (pinfunction "PLLIN_18") (pintype "passive+no_connect"))
    )
  )
)
